# Turnstile.net
KiCad netlist of a schematic drawn in EAGLE
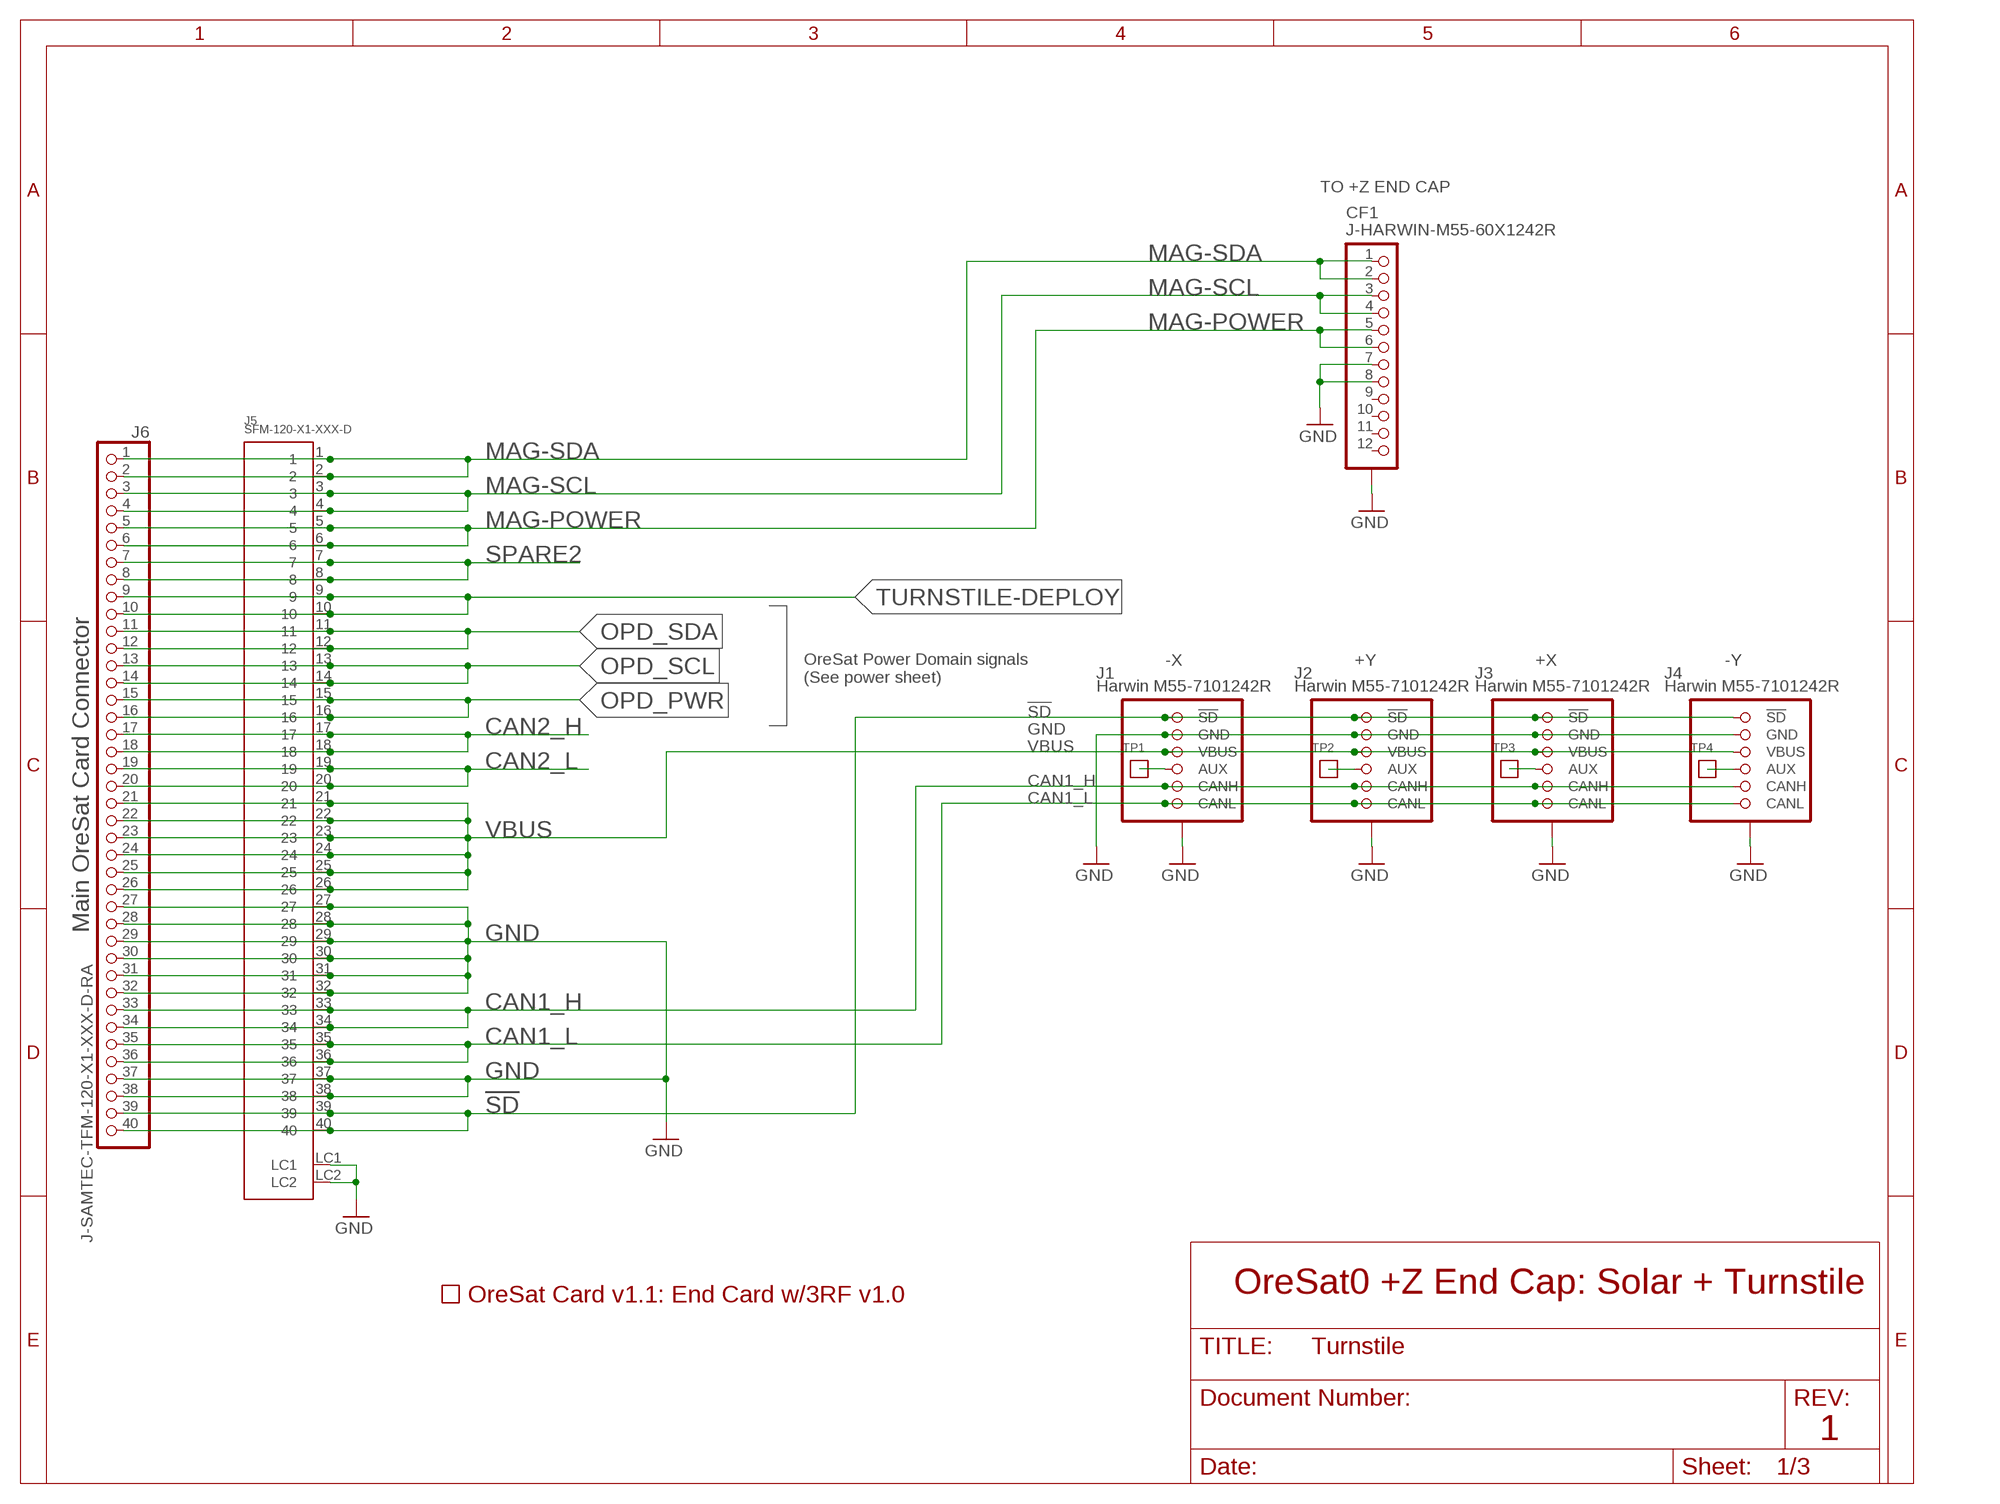
[diagram p0: schematic, sheet 1]
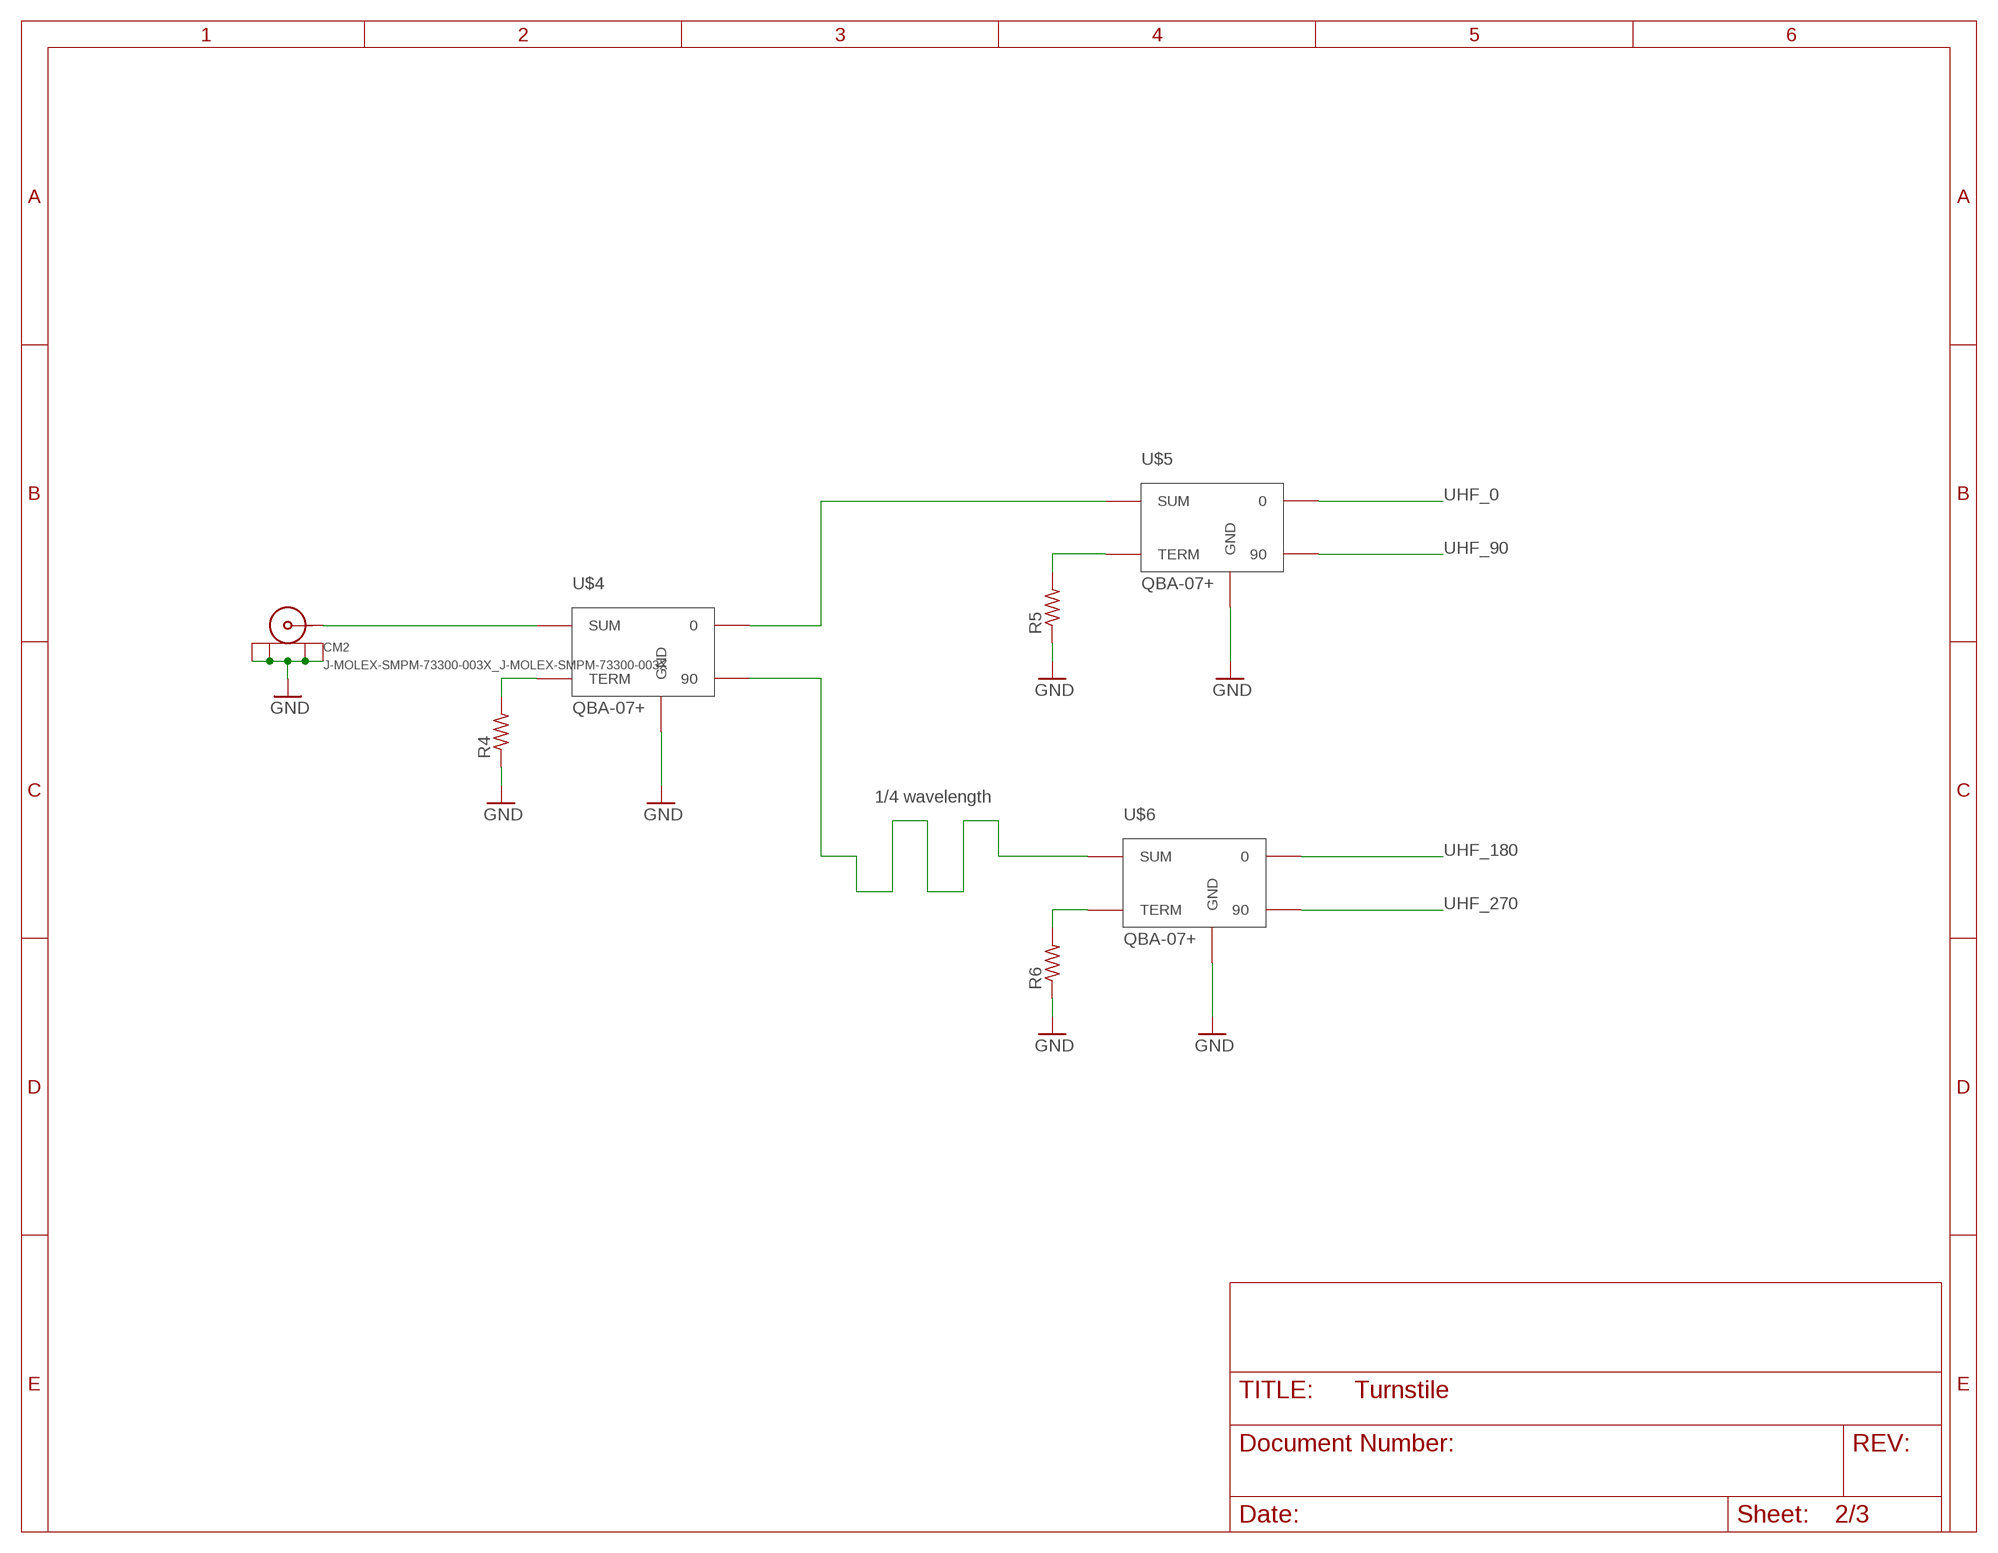
[diagram p1: schematic, sheet 2]
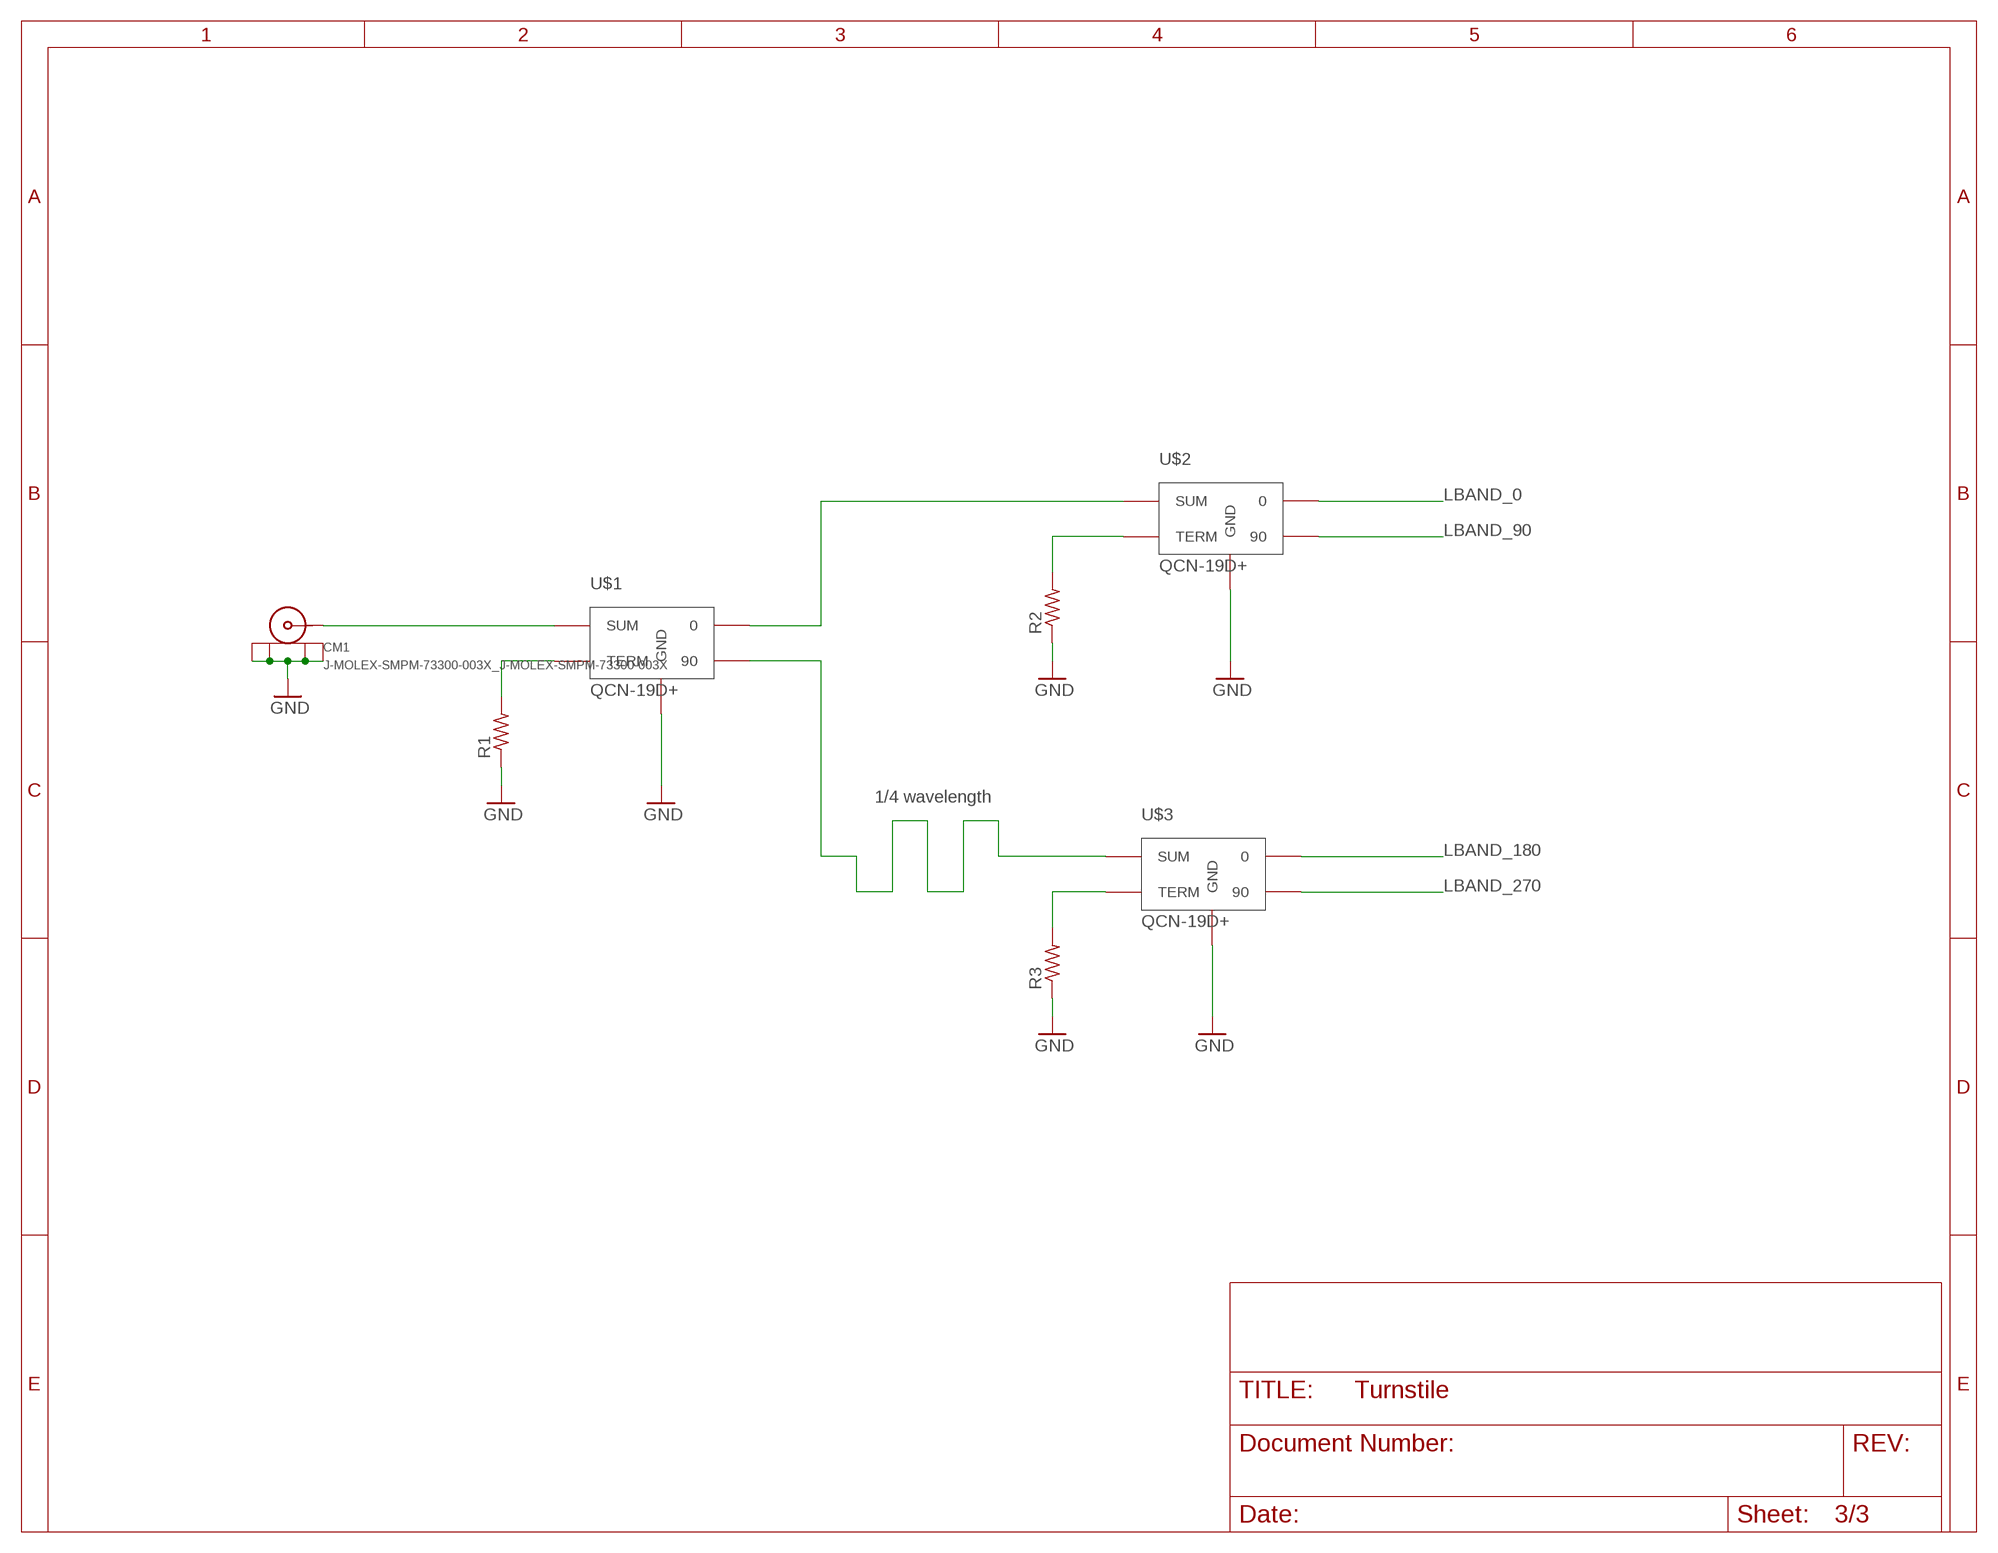
[diagram p2: schematic, sheet 3]

(export (version "E")
  (design (tool "Eeschema 10.0.6"))
  (components
    (comp (ref "CM1")
      (value "J-MOLEX-SMPM-73300-003X_J-MOLEX-SMPM-73300-003X")
      (footprint "eagle-import:J-MOLEX-SMPM-73300-003X_J-MOLEX-SMPM-073300-003X")
      (libsource (lib "eagle-import") (part "J-MOLEX-SMPM-73300-003X_J-MOLEX-SMPM-73300-003X"))
    )
    (comp (ref "R1")
      (value "R-US_0402-A-NOSILK")
      (footprint "eagle-import:.0402-A-NOSILK")
      (libsource (lib "eagle-import") (part "R-US_0402-A-NOSILK"))
    )
    (comp (ref "R2")
      (value "R-US_0402-A-NOSILK")
      (footprint "eagle-import:.0402-A-NOSILK")
      (libsource (lib "eagle-import") (part "R-US_0402-A-NOSILK"))
    )
    (comp (ref "R3")
      (value "R-US_0402-A-NOSILK")
      (footprint "eagle-import:.0402-A-NOSILK")
      (libsource (lib "eagle-import") (part "R-US_0402-A-NOSILK"))
    )
    (comp (ref "U$1")
      (value "QCN-19D+")
      (footprint "eagle-import:QVN-19D+")
      (libsource (lib "eagle-import") (part "QCN-19D+"))
    )
    (comp (ref "U$2")
      (value "QCN-19D+")
      (footprint "eagle-import:QVN-19D+")
      (libsource (lib "eagle-import") (part "QCN-19D+"))
    )
    (comp (ref "U$3")
      (value "QCN-19D+")
      (footprint "eagle-import:QVN-19D+")
      (libsource (lib "eagle-import") (part "QCN-19D+"))
    )
    (comp (ref "CM2")
      (value "J-MOLEX-SMPM-73300-003X_J-MOLEX-SMPM-73300-003X")
      (footprint "eagle-import:J-MOLEX-SMPM-73300-003X_J-MOLEX-SMPM-073300-003X")
      (libsource (lib "eagle-import") (part "J-MOLEX-SMPM-73300-003X_J-MOLEX-SMPM-73300-003X"))
    )
    (comp (ref "R4")
      (value "R-US_0402-A-NOSILK")
      (footprint "eagle-import:.0402-A-NOSILK")
      (libsource (lib "eagle-import") (part "R-US_0402-A-NOSILK"))
    )
    (comp (ref "R5")
      (value "R-US_0402-A-NOSILK")
      (footprint "eagle-import:.0402-A-NOSILK")
      (libsource (lib "eagle-import") (part "R-US_0402-A-NOSILK"))
    )
    (comp (ref "R6")
      (value "R-US_0402-A-NOSILK")
      (footprint "eagle-import:.0402-A-NOSILK")
      (libsource (lib "eagle-import") (part "R-US_0402-A-NOSILK"))
    )
    (comp (ref "U$4")
      (value "QBA-07+")
      (footprint "eagle-import:QBA-07+")
      (libsource (lib "eagle-import") (part "QBA-07+"))
    )
    (comp (ref "U$5")
      (value "QBA-07+")
      (footprint "eagle-import:QBA-07+")
      (libsource (lib "eagle-import") (part "QBA-07+"))
    )
    (comp (ref "U$6")
      (value "QBA-07+")
      (footprint "eagle-import:QBA-07+")
      (libsource (lib "eagle-import") (part "QBA-07+"))
    )
    (comp (ref "CF1")
      (value "J-HARWIN-M55-60X1242R")
      (footprint "eagle-import:HARWIN-M55-60X1242R")
      (libsource (lib "eagle-import") (part "J-HARWIN-M55-60X1242R"))
    )
    (comp (ref "J1")
      (value "Harwin M55-7101242R")
      (footprint "eagle-import:M55-7101242R")
      (libsource (lib "eagle-import") (part "SOLAR-CARD-CONNECTOR"))
    )
    (comp (ref "J2")
      (value "Harwin M55-7101242R")
      (footprint "eagle-import:M55-7101242R")
      (libsource (lib "eagle-import") (part "SOLAR-CARD-CONNECTOR"))
    )
    (comp (ref "J3")
      (value "Harwin M55-7101242R")
      (footprint "eagle-import:M55-7101242R")
      (libsource (lib "eagle-import") (part "SOLAR-CARD-CONNECTOR"))
    )
    (comp (ref "J4")
      (value "Harwin M55-7101242R")
      (footprint "eagle-import:M55-7101242R")
      (libsource (lib "eagle-import") (part "SOLAR-CARD-CONNECTOR"))
    )
    (comp (ref "J5")
      (value "SFM-120-X1-XXX-D")
      (footprint "eagle-import:SFM-120-X1-XXX-D")
      (libsource (lib "eagle-import") (part "SFM-120-X1-XXX-D"))
    )
    (comp (ref "J6")
      (value "J-SAMTEC-TFM-120-X1-XXX-D-RA")
      (footprint "eagle-import:J-SAMTEC-TFM-120-X1-XXX-D-RA")
      (fields (field (name "MFR") "Samtec") (field (name "MPN") "TFM-120-01-L-D-RA"))
      (libsource (lib "eagle-import") (part "J-SAMTEC-TFM-120-X1-XXX-D-RA"))
    )
    (comp (ref "PCB1")
      (value "ORESAT-CARD-V1.1-END-CARD-3RF-V1.0")
      (footprint "eagle-import:ORESAT-CARDV1.1-END-CARD-3RF-V1.0")
      (libsource (lib "eagle-import") (part "ORESAT-CARD-V1.1-END-CARD-3RF-V1.0"))
    )
    (comp (ref "TP1")
      (value "TEST-POINT-LARGE-SQUARE")
      (footprint "eagle-import:1X01")
      (libsource (lib "eagle-import") (part "TEST-POINT-LARGE-SQUARE"))
    )
    (comp (ref "TP2")
      (value "TEST-POINT-LARGE-SQUARE")
      (footprint "eagle-import:1X01")
      (libsource (lib "eagle-import") (part "TEST-POINT-LARGE-SQUARE"))
    )
    (comp (ref "TP3")
      (value "TEST-POINT-LARGE-SQUARE")
      (footprint "eagle-import:1X01")
      (libsource (lib "eagle-import") (part "TEST-POINT-LARGE-SQUARE"))
    )
    (comp (ref "TP4")
      (value "TEST-POINT-LARGE-SQUARE")
      (footprint "eagle-import:1X01")
      (libsource (lib "eagle-import") (part "TEST-POINT-LARGE-SQUARE"))
    )
  )
  (nets
    (net (code "1") (name "CAN1_H") (class "Default")
      (node (ref "J1") (pin "10") (pinfunction "CANH_10") (pintype "passive"))
      (node (ref "J1") (pin "9") (pinfunction "CANH_9") (pintype "passive"))
      (node (ref "J2") (pin "10") (pinfunction "CANH_10") (pintype "passive"))
      (node (ref "J2") (pin "9") (pinfunction "CANH_9") (pintype "passive"))
      (node (ref "J3") (pin "10") (pinfunction "CANH_10") (pintype "passive"))
      (node (ref "J3") (pin "9") (pinfunction "CANH_9") (pintype "passive"))
      (node (ref "J4") (pin "10") (pinfunction "CANH_10") (pintype "passive"))
      (node (ref "J4") (pin "9") (pinfunction "CANH_9") (pintype "passive"))
      (node (ref "J5") (pin "33") (pinfunction "33_33") (pintype "passive"))
      (node (ref "J5") (pin "34") (pinfunction "34_34") (pintype "passive"))
      (node (ref "J6") (pin "33") (pinfunction "33_33") (pintype "passive"))
      (node (ref "J6") (pin "34") (pinfunction "34_34") (pintype "passive"))
    )
    (net (code "2") (name "CAN1_L") (class "Default")
      (node (ref "J1") (pin "11") (pinfunction "CANL_11") (pintype "passive"))
      (node (ref "J1") (pin "12") (pinfunction "CANL_12") (pintype "passive"))
      (node (ref "J2") (pin "11") (pinfunction "CANL_11") (pintype "passive"))
      (node (ref "J2") (pin "12") (pinfunction "CANL_12") (pintype "passive"))
      (node (ref "J3") (pin "11") (pinfunction "CANL_11") (pintype "passive"))
      (node (ref "J3") (pin "12") (pinfunction "CANL_12") (pintype "passive"))
      (node (ref "J4") (pin "11") (pinfunction "CANL_11") (pintype "passive"))
      (node (ref "J4") (pin "12") (pinfunction "CANL_12") (pintype "passive"))
      (node (ref "J5") (pin "35") (pinfunction "35_35") (pintype "passive"))
      (node (ref "J5") (pin "36") (pinfunction "36_36") (pintype "passive"))
      (node (ref "J6") (pin "35") (pinfunction "35_35") (pintype "passive"))
      (node (ref "J6") (pin "36") (pinfunction "36_36") (pintype "passive"))
    )
    (net (code "3") (name "CAN2_H") (class "Default")
      (node (ref "J5") (pin "17") (pinfunction "17_17") (pintype "passive"))
      (node (ref "J5") (pin "18") (pinfunction "18_18") (pintype "passive"))
      (node (ref "J6") (pin "17") (pinfunction "17_17") (pintype "passive"))
      (node (ref "J6") (pin "18") (pinfunction "18_18") (pintype "passive"))
    )
    (net (code "4") (name "CAN2_L") (class "Default")
      (node (ref "J5") (pin "19") (pinfunction "19_19") (pintype "passive"))
      (node (ref "J5") (pin "20") (pinfunction "20_20") (pintype "passive"))
      (node (ref "J6") (pin "19") (pinfunction "19_19") (pintype "passive"))
      (node (ref "J6") (pin "20") (pinfunction "20_20") (pintype "passive"))
    )
    (net (code "5") (name "GND") (class "Default")
      (node (ref "CF1") (pin "7") (pinfunction "7_7") (pintype "passive"))
      (node (ref "CF1") (pin "8") (pinfunction "8_8") (pintype "passive"))
      (node (ref "CF1") (pin "P$1") (pinfunction "SHIELDS_P$1") (pintype "passive"))
      (node (ref "CF1") (pin "P$2") (pinfunction "SHIELDS_P$2") (pintype "passive"))
      (node (ref "CF1") (pin "P$3") (pinfunction "SHIELDS_P$3") (pintype "passive"))
      (node (ref "CF1") (pin "P$4") (pinfunction "SHIELDS_P$4") (pintype "passive"))
      (node (ref "CM1") (pin "P$1") (pinfunction "SHIELD3_P$1") (pintype "passive"))
      (node (ref "CM1") (pin "P$2") (pinfunction "SHIELD2_P$2") (pintype "passive"))
      (node (ref "CM1") (pin "P$3") (pinfunction "SHIELD1_P$3") (pintype "passive"))
      (node (ref "CM1") (pin "P$4") (pinfunction "SHIELD_P$4") (pintype "passive"))
      (node (ref "CM2") (pin "P$1") (pinfunction "SHIELD3_P$1") (pintype "passive"))
      (node (ref "CM2") (pin "P$2") (pinfunction "SHIELD2_P$2") (pintype "passive"))
      (node (ref "CM2") (pin "P$3") (pinfunction "SHIELD1_P$3") (pintype "passive"))
      (node (ref "CM2") (pin "P$4") (pinfunction "SHIELD_P$4") (pintype "passive"))
      (node (ref "J1") (pin "3") (pinfunction "GND_3") (pintype "passive"))
      (node (ref "J1") (pin "4") (pinfunction "GND_4") (pintype "passive"))
      (node (ref "J1") (pin "P$1") (pinfunction "SHIELD_P$1") (pintype "passive"))
      (node (ref "J1") (pin "P$2") (pinfunction "SHIELD_P$2") (pintype "passive"))
      (node (ref "J1") (pin "P$3") (pinfunction "SHIELD_P$3") (pintype "passive"))
      (node (ref "J1") (pin "P$4") (pinfunction "SHIELD_P$4") (pintype "passive"))
      (node (ref "J2") (pin "3") (pinfunction "GND_3") (pintype "passive"))
      (node (ref "J2") (pin "4") (pinfunction "GND_4") (pintype "passive"))
      (node (ref "J2") (pin "P$1") (pinfunction "SHIELD_P$1") (pintype "passive"))
      (node (ref "J2") (pin "P$2") (pinfunction "SHIELD_P$2") (pintype "passive"))
      (node (ref "J2") (pin "P$3") (pinfunction "SHIELD_P$3") (pintype "passive"))
      (node (ref "J2") (pin "P$4") (pinfunction "SHIELD_P$4") (pintype "passive"))
      (node (ref "J3") (pin "3") (pinfunction "GND_3") (pintype "passive"))
      (node (ref "J3") (pin "4") (pinfunction "GND_4") (pintype "passive"))
      (node (ref "J3") (pin "P$1") (pinfunction "SHIELD_P$1") (pintype "passive"))
      (node (ref "J3") (pin "P$2") (pinfunction "SHIELD_P$2") (pintype "passive"))
      (node (ref "J3") (pin "P$3") (pinfunction "SHIELD_P$3") (pintype "passive"))
      (node (ref "J3") (pin "P$4") (pinfunction "SHIELD_P$4") (pintype "passive"))
      (node (ref "J4") (pin "3") (pinfunction "GND_3") (pintype "passive"))
      (node (ref "J4") (pin "4") (pinfunction "GND_4") (pintype "passive"))
      (node (ref "J4") (pin "P$1") (pinfunction "SHIELD_P$1") (pintype "passive"))
      (node (ref "J4") (pin "P$2") (pinfunction "SHIELD_P$2") (pintype "passive"))
      (node (ref "J4") (pin "P$3") (pinfunction "SHIELD_P$3") (pintype "passive"))
      (node (ref "J4") (pin "P$4") (pinfunction "SHIELD_P$4") (pintype "passive"))
      (node (ref "J5") (pin "27") (pinfunction "27_27") (pintype "passive"))
      (node (ref "J5") (pin "28") (pinfunction "28_28") (pintype "passive"))
      (node (ref "J5") (pin "29") (pinfunction "29_29") (pintype "passive"))
      (node (ref "J5") (pin "30") (pinfunction "30_30") (pintype "passive"))
      (node (ref "J5") (pin "31") (pinfunction "31_31") (pintype "passive"))
      (node (ref "J5") (pin "32") (pinfunction "32_32") (pintype "passive"))
      (node (ref "J5") (pin "37") (pinfunction "37_37") (pintype "passive"))
      (node (ref "J5") (pin "38") (pinfunction "38_38") (pintype "passive"))
      (node (ref "J5") (pin "LC1") (pinfunction "LC1_LC1") (pintype "passive"))
      (node (ref "J5") (pin "LC2") (pinfunction "LC2_LC2") (pintype "passive"))
      (node (ref "J6") (pin "27") (pinfunction "27_27") (pintype "passive"))
      (node (ref "J6") (pin "28") (pinfunction "28_28") (pintype "passive"))
      (node (ref "J6") (pin "29") (pinfunction "29_29") (pintype "passive"))
      (node (ref "J6") (pin "30") (pinfunction "30_30") (pintype "passive"))
      (node (ref "J6") (pin "31") (pinfunction "31_31") (pintype "passive"))
      (node (ref "J6") (pin "32") (pinfunction "32_32") (pintype "passive"))
      (node (ref "J6") (pin "37") (pinfunction "37_37") (pintype "passive"))
      (node (ref "J6") (pin "38") (pinfunction "38_38") (pintype "passive"))
      (node (ref "R1") (pin "1") (pinfunction "1_1") (pintype "passive"))
      (node (ref "R2") (pin "1") (pinfunction "1_1") (pintype "passive"))
      (node (ref "R3") (pin "1") (pinfunction "1_1") (pintype "passive"))
      (node (ref "R4") (pin "1") (pinfunction "1_1") (pintype "passive"))
      (node (ref "R5") (pin "1") (pinfunction "1_1") (pintype "passive"))
      (node (ref "R6") (pin "1") (pinfunction "1_1") (pintype "passive"))
      (node (ref "U$1") (pin "P$2") (pinfunction "GND_P$2") (pintype "bidirectional"))
      (node (ref "U$1") (pin "P$5") (pinfunction "GND_P$5") (pintype "bidirectional"))
      (node (ref "U$2") (pin "P$2") (pinfunction "GND_P$2") (pintype "bidirectional"))
      (node (ref "U$2") (pin "P$5") (pinfunction "GND_P$5") (pintype "bidirectional"))
      (node (ref "U$3") (pin "P$2") (pinfunction "GND_P$2") (pintype "bidirectional"))
      (node (ref "U$3") (pin "P$5") (pinfunction "GND_P$5") (pintype "bidirectional"))
      (node (ref "U$4") (pin "P$11") (pinfunction "GND_P$11") (pintype "bidirectional"))
      (node (ref "U$4") (pin "P$2") (pinfunction "GND_P$2") (pintype "bidirectional"))
      (node (ref "U$4") (pin "P$3") (pinfunction "GND_P$3") (pintype "bidirectional"))
      (node (ref "U$4") (pin "P$4") (pinfunction "GND_P$4") (pintype "bidirectional"))
      (node (ref "U$4") (pin "P$7") (pinfunction "GND_P$7") (pintype "bidirectional"))
      (node (ref "U$4") (pin "P$8") (pinfunction "GND_P$8") (pintype "bidirectional"))
      (node (ref "U$4") (pin "P$9") (pinfunction "GND_P$9") (pintype "bidirectional"))
      (node (ref "U$5") (pin "P$11") (pinfunction "GND_P$11") (pintype "bidirectional"))
      (node (ref "U$5") (pin "P$2") (pinfunction "GND_P$2") (pintype "bidirectional"))
      (node (ref "U$5") (pin "P$3") (pinfunction "GND_P$3") (pintype "bidirectional"))
      (node (ref "U$5") (pin "P$4") (pinfunction "GND_P$4") (pintype "bidirectional"))
      (node (ref "U$5") (pin "P$7") (pinfunction "GND_P$7") (pintype "bidirectional"))
      (node (ref "U$5") (pin "P$8") (pinfunction "GND_P$8") (pintype "bidirectional"))
      (node (ref "U$5") (pin "P$9") (pinfunction "GND_P$9") (pintype "bidirectional"))
      (node (ref "U$6") (pin "P$11") (pinfunction "GND_P$11") (pintype "bidirectional"))
      (node (ref "U$6") (pin "P$2") (pinfunction "GND_P$2") (pintype "bidirectional"))
      (node (ref "U$6") (pin "P$3") (pinfunction "GND_P$3") (pintype "bidirectional"))
      (node (ref "U$6") (pin "P$4") (pinfunction "GND_P$4") (pintype "bidirectional"))
      (node (ref "U$6") (pin "P$7") (pinfunction "GND_P$7") (pintype "bidirectional"))
      (node (ref "U$6") (pin "P$8") (pinfunction "GND_P$8") (pintype "bidirectional"))
      (node (ref "U$6") (pin "P$9") (pinfunction "GND_P$9") (pintype "bidirectional"))
    )
    (net (code "6") (name "LBAND_0") (class "Default")
      (node (ref "U$2") (pin "P$4") (pinfunction "0_P$4") (pintype "bidirectional"))
    )
    (net (code "7") (name "LBAND_90") (class "Default")
      (node (ref "U$2") (pin "P$6") (pinfunction "90_P$6") (pintype "bidirectional"))
    )
    (net (code "8") (name "LBAND_180") (class "Default")
      (node (ref "U$3") (pin "P$4") (pinfunction "0_P$4") (pintype "bidirectional"))
    )
    (net (code "9") (name "LBAND_270") (class "Default")
      (node (ref "U$3") (pin "P$6") (pinfunction "90_P$6") (pintype "bidirectional"))
    )
    (net (code "10") (name "MAG-POWER") (class "Default")
      (node (ref "CF1") (pin "5") (pinfunction "5_5") (pintype "passive"))
      (node (ref "CF1") (pin "6") (pinfunction "6_6") (pintype "passive"))
      (node (ref "J5") (pin "5") (pinfunction "5_5") (pintype "passive"))
      (node (ref "J5") (pin "6") (pinfunction "6_6") (pintype "passive"))
      (node (ref "J6") (pin "5") (pinfunction "5_5") (pintype "passive"))
      (node (ref "J6") (pin "6") (pinfunction "6_6") (pintype "passive"))
    )
    (net (code "11") (name "MAG-SCL") (class "Default")
      (node (ref "CF1") (pin "3") (pinfunction "3_3") (pintype "passive"))
      (node (ref "CF1") (pin "4") (pinfunction "4_4") (pintype "passive"))
      (node (ref "J5") (pin "3") (pinfunction "3_3") (pintype "passive"))
      (node (ref "J5") (pin "4") (pinfunction "4_4") (pintype "passive"))
      (node (ref "J6") (pin "3") (pinfunction "3_3") (pintype "passive"))
      (node (ref "J6") (pin "4") (pinfunction "4_4") (pintype "passive"))
    )
    (net (code "12") (name "MAG-SDA") (class "Default")
      (node (ref "CF1") (pin "1") (pinfunction "1_1") (pintype "passive"))
      (node (ref "CF1") (pin "2") (pinfunction "2_2") (pintype "passive"))
      (node (ref "J5") (pin "1") (pinfunction "1_1") (pintype "passive"))
      (node (ref "J5") (pin "2") (pinfunction "2_2") (pintype "passive"))
      (node (ref "J6") (pin "1") (pinfunction "1_1") (pintype "passive"))
      (node (ref "J6") (pin "2") (pinfunction "2_2") (pintype "passive"))
    )
    (net (code "13") (name "Net-(CM1-CENTER)") (class "Default")
      (node (ref "CM1") (pin "RF") (pinfunction "CENTER_RF") (pintype "passive"))
      (node (ref "U$1") (pin "P$1") (pinfunction "SUM_P$1") (pintype "bidirectional"))
    )
    (net (code "14") (name "Net-(CM2-CENTER)") (class "Default")
      (node (ref "CM2") (pin "RF") (pinfunction "CENTER_RF") (pintype "passive"))
      (node (ref "U$4") (pin "P$1") (pinfunction "SUM_P$1") (pintype "bidirectional"))
    )
    (net (code "15") (name "Net-(J1-AUX-Pad7)") (class "Default")
      (node (ref "J1") (pin "7") (pinfunction "AUX_7") (pintype "passive"))
      (node (ref "J1") (pin "8") (pinfunction "AUX_8") (pintype "passive"))
      (node (ref "TP1") (pin "1") (pinfunction "1_1") (pintype "passive"))
    )
    (net (code "16") (name "Net-(J2-AUX-Pad7)") (class "Default")
      (node (ref "J2") (pin "7") (pinfunction "AUX_7") (pintype "passive"))
      (node (ref "J2") (pin "8") (pinfunction "AUX_8") (pintype "passive"))
      (node (ref "TP2") (pin "1") (pinfunction "1_1") (pintype "passive"))
    )
    (net (code "17") (name "Net-(J3-AUX-Pad7)") (class "Default")
      (node (ref "J3") (pin "7") (pinfunction "AUX_7") (pintype "passive"))
      (node (ref "J3") (pin "8") (pinfunction "AUX_8") (pintype "passive"))
      (node (ref "TP3") (pin "1") (pinfunction "1_1") (pintype "passive"))
    )
    (net (code "18") (name "Net-(J4-AUX-Pad7)") (class "Default")
      (node (ref "J4") (pin "7") (pinfunction "AUX_7") (pintype "passive"))
      (node (ref "J4") (pin "8") (pinfunction "AUX_8") (pintype "passive"))
      (node (ref "TP4") (pin "1") (pinfunction "1_1") (pintype "passive"))
    )
    (net (code "19") (name "Net-(U$1-0)") (class "Default")
      (node (ref "U$1") (pin "P$4") (pinfunction "0_P$4") (pintype "bidirectional"))
      (node (ref "U$2") (pin "P$1") (pinfunction "SUM_P$1") (pintype "bidirectional"))
    )
    (net (code "20") (name "Net-(U$1-90)") (class "Default")
      (node (ref "U$1") (pin "P$6") (pinfunction "90_P$6") (pintype "bidirectional"))
      (node (ref "U$3") (pin "P$1") (pinfunction "SUM_P$1") (pintype "bidirectional"))
    )
    (net (code "21") (name "Net-(U$1-TERM)") (class "Default")
      (node (ref "R1") (pin "2") (pinfunction "2_2") (pintype "passive"))
      (node (ref "U$1") (pin "P$3") (pinfunction "TERM_P$3") (pintype "bidirectional"))
    )
    (net (code "22") (name "Net-(U$2-TERM)") (class "Default")
      (node (ref "R2") (pin "2") (pinfunction "2_2") (pintype "passive"))
      (node (ref "U$2") (pin "P$3") (pinfunction "TERM_P$3") (pintype "bidirectional"))
    )
    (net (code "23") (name "Net-(U$3-TERM)") (class "Default")
      (node (ref "R3") (pin "2") (pinfunction "2_2") (pintype "passive"))
      (node (ref "U$3") (pin "P$3") (pinfunction "TERM_P$3") (pintype "bidirectional"))
    )
    (net (code "24") (name "Net-(U$4-0)") (class "Default")
      (node (ref "U$4") (pin "P$6") (pinfunction "0_P$6") (pintype "bidirectional"))
      (node (ref "U$5") (pin "P$1") (pinfunction "SUM_P$1") (pintype "bidirectional"))
    )
    (net (code "25") (name "Net-(U$4-90)") (class "Default")
      (node (ref "U$4") (pin "P$10") (pinfunction "90_P$10") (pintype "bidirectional"))
      (node (ref "U$6") (pin "P$1") (pinfunction "SUM_P$1") (pintype "bidirectional"))
    )
    (net (code "26") (name "Net-(U$4-TERM)") (class "Default")
      (node (ref "R4") (pin "2") (pinfunction "2_2") (pintype "passive"))
      (node (ref "U$4") (pin "P$5") (pinfunction "TERM_P$5") (pintype "bidirectional"))
    )
    (net (code "27") (name "Net-(U$5-TERM)") (class "Default")
      (node (ref "R5") (pin "2") (pinfunction "2_2") (pintype "passive"))
      (node (ref "U$5") (pin "P$5") (pinfunction "TERM_P$5") (pintype "bidirectional"))
    )
    (net (code "28") (name "Net-(U$6-TERM)") (class "Default")
      (node (ref "R6") (pin "2") (pinfunction "2_2") (pintype "passive"))
      (node (ref "U$6") (pin "P$5") (pinfunction "TERM_P$5") (pintype "bidirectional"))
    )
    (net (code "29") (name "OPD_PWR") (class "Default")
      (node (ref "J5") (pin "15") (pinfunction "15_15") (pintype "passive"))
      (node (ref "J5") (pin "16") (pinfunction "16_16") (pintype "passive"))
      (node (ref "J6") (pin "15") (pinfunction "15_15") (pintype "passive"))
      (node (ref "J6") (pin "16") (pinfunction "16_16") (pintype "passive"))
    )
    (net (code "30") (name "OPD_SCL") (class "Default")
      (node (ref "J5") (pin "13") (pinfunction "13_13") (pintype "passive"))
      (node (ref "J5") (pin "14") (pinfunction "14_14") (pintype "passive"))
      (node (ref "J6") (pin "13") (pinfunction "13_13") (pintype "passive"))
      (node (ref "J6") (pin "14") (pinfunction "14_14") (pintype "passive"))
    )
    (net (code "31") (name "OPD_SDA") (class "Default")
      (node (ref "J5") (pin "11") (pinfunction "11_11") (pintype "passive"))
      (node (ref "J5") (pin "12") (pinfunction "12_12") (pintype "passive"))
      (node (ref "J6") (pin "11") (pinfunction "11_11") (pintype "passive"))
      (node (ref "J6") (pin "12") (pinfunction "12_12") (pintype "passive"))
    )
    (net (code "32") (name "SPARE2") (class "Default")
      (node (ref "J5") (pin "7") (pinfunction "7_7") (pintype "passive"))
      (node (ref "J5") (pin "8") (pinfunction "8_8") (pintype "passive"))
      (node (ref "J6") (pin "7") (pinfunction "7_7") (pintype "passive"))
      (node (ref "J6") (pin "8") (pinfunction "8_8") (pintype "passive"))
    )
    (net (code "33") (name "TURNSTILE-DEPLOY") (class "Default")
      (node (ref "J5") (pin "10") (pinfunction "10_10") (pintype "passive"))
      (node (ref "J5") (pin "9") (pinfunction "9_9") (pintype "passive"))
      (node (ref "J6") (pin "10") (pinfunction "10_10") (pintype "passive"))
      (node (ref "J6") (pin "9") (pinfunction "9_9") (pintype "passive"))
    )
    (net (code "34") (name "UHF_0") (class "Default")
      (node (ref "U$5") (pin "P$6") (pinfunction "0_P$6") (pintype "bidirectional"))
    )
    (net (code "35") (name "UHF_90") (class "Default")
      (node (ref "U$5") (pin "P$10") (pinfunction "90_P$10") (pintype "bidirectional"))
    )
    (net (code "36") (name "UHF_180") (class "Default")
      (node (ref "U$6") (pin "P$6") (pinfunction "0_P$6") (pintype "bidirectional"))
    )
    (net (code "37") (name "UHF_270") (class "Default")
      (node (ref "U$6") (pin "P$10") (pinfunction "90_P$10") (pintype "bidirectional"))
    )
    (net (code "38") (name "VBUS") (class "Default")
      (node (ref "J1") (pin "5") (pinfunction "VBUS_5") (pintype "passive"))
      (node (ref "J1") (pin "6") (pinfunction "VBUS_6") (pintype "passive"))
      (node (ref "J2") (pin "5") (pinfunction "VBUS_5") (pintype "passive"))
      (node (ref "J2") (pin "6") (pinfunction "VBUS_6") (pintype "passive"))
      (node (ref "J3") (pin "5") (pinfunction "VBUS_5") (pintype "passive"))
      (node (ref "J3") (pin "6") (pinfunction "VBUS_6") (pintype "passive"))
      (node (ref "J4") (pin "5") (pinfunction "VBUS_5") (pintype "passive"))
      (node (ref "J4") (pin "6") (pinfunction "VBUS_6") (pintype "passive"))
      (node (ref "J5") (pin "21") (pinfunction "21_21") (pintype "passive"))
      (node (ref "J5") (pin "22") (pinfunction "22_22") (pintype "passive"))
      (node (ref "J5") (pin "23") (pinfunction "23_23") (pintype "passive"))
      (node (ref "J5") (pin "24") (pinfunction "24_24") (pintype "passive"))
      (node (ref "J5") (pin "25") (pinfunction "25_25") (pintype "passive"))
      (node (ref "J5") (pin "26") (pinfunction "26_26") (pintype "passive"))
      (node (ref "J6") (pin "21") (pinfunction "21_21") (pintype "passive"))
      (node (ref "J6") (pin "22") (pinfunction "22_22") (pintype "passive"))
      (node (ref "J6") (pin "23") (pinfunction "23_23") (pintype "passive"))
      (node (ref "J6") (pin "24") (pinfunction "24_24") (pintype "passive"))
      (node (ref "J6") (pin "25") (pinfunction "25_25") (pintype "passive"))
      (node (ref "J6") (pin "26") (pinfunction "26_26") (pintype "passive"))
    )
    (net (code "39") (name "unconnected-(CF1-Pad9)") (class "Default")
      (node (ref "CF1") (pin "9") (pinfunction "9_9") (pintype "passive"))
    )
    (net (code "40") (name "unconnected-(CF1-Pad10)") (class "Default")
      (node (ref "CF1") (pin "10") (pinfunction "10_10") (pintype "passive"))
    )
    (net (code "41") (name "unconnected-(CF1-Pad11)") (class "Default")
      (node (ref "CF1") (pin "11") (pinfunction "11_11") (pintype "passive"))
    )
    (net (code "42") (name "unconnected-(CF1-Pad12)") (class "Default")
      (node (ref "CF1") (pin "12") (pinfunction "12_12") (pintype "passive"))
    )
    (net (code "43") (name "~{SD}") (class "Default")
      (node (ref "J1") (pin "1") (pinfunction "~{SD}_1") (pintype "passive"))
      (node (ref "J1") (pin "2") (pinfunction "~{SD}_2") (pintype "passive"))
      (node (ref "J2") (pin "1") (pinfunction "~{SD}_1") (pintype "passive"))
      (node (ref "J2") (pin "2") (pinfunction "~{SD}_2") (pintype "passive"))
      (node (ref "J3") (pin "1") (pinfunction "~{SD}_1") (pintype "passive"))
      (node (ref "J3") (pin "2") (pinfunction "~{SD}_2") (pintype "passive"))
      (node (ref "J4") (pin "1") (pinfunction "~{SD}_1") (pintype "passive"))
      (node (ref "J4") (pin "2") (pinfunction "~{SD}_2") (pintype "passive"))
      (node (ref "J5") (pin "39") (pinfunction "39_39") (pintype "passive"))
      (node (ref "J5") (pin "40") (pinfunction "40_40") (pintype "passive"))
      (node (ref "J6") (pin "39") (pinfunction "39_39") (pintype "passive"))
      (node (ref "J6") (pin "40") (pinfunction "40_40") (pintype "passive"))
    )
  )
)
